# TSAL.net
KiCad netlist of a schematic drawn in Altium Designer
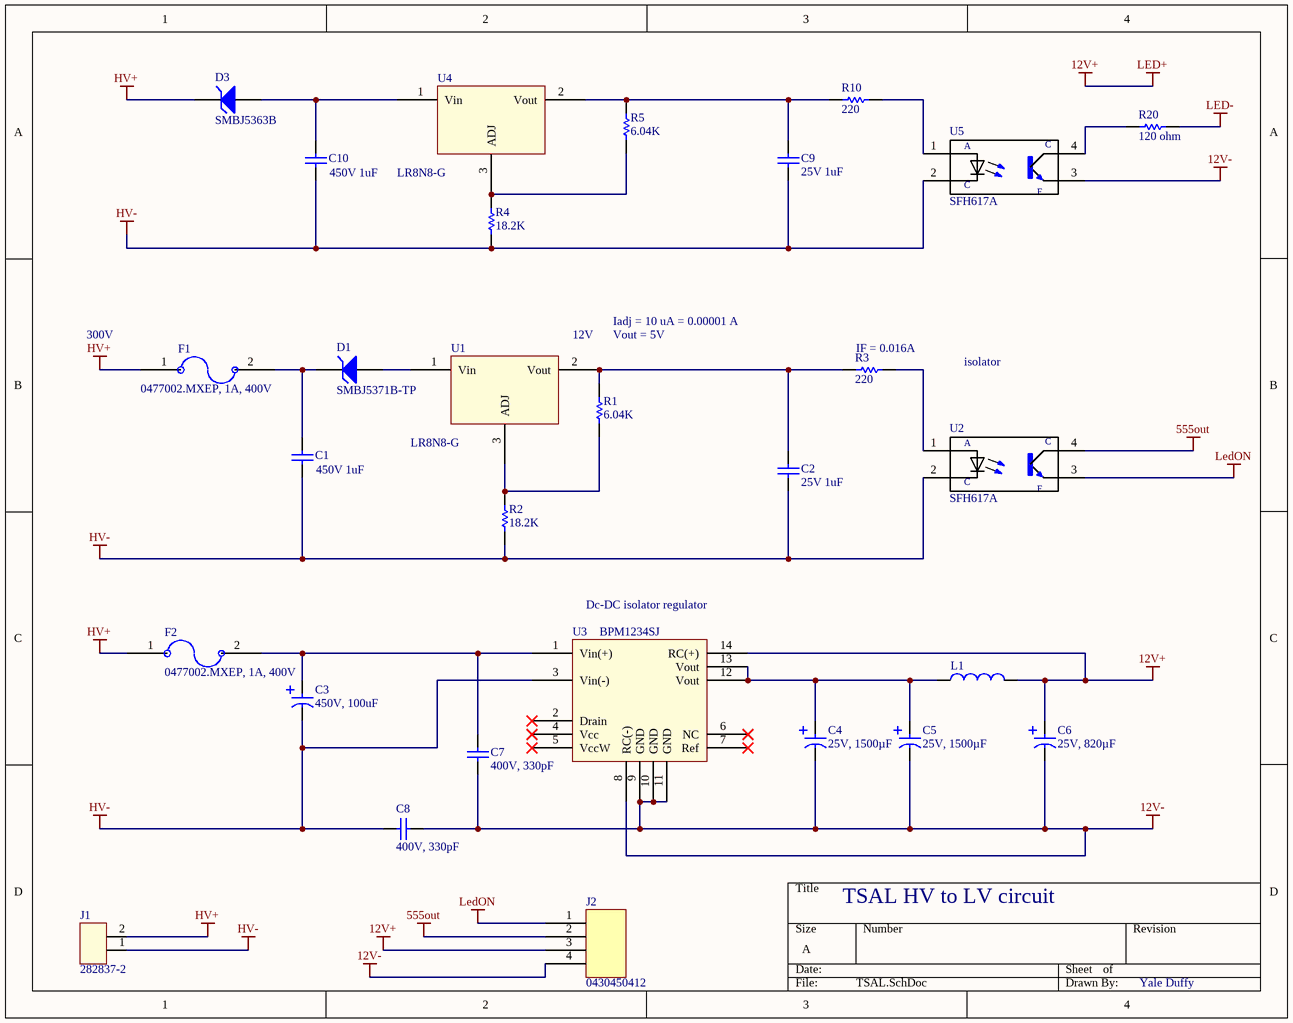
[diagram p0: TSAL.SchDoc]

(export (version "E")
  (design (tool "Eeschema 10.0.6"))
  (components
    (comp (ref "C1")
      (value "450V 1uF")
      (footprint "CKG57KX7T2W105K335JH")
      (description "Decoupling capacitor")
      (libsource (lib "schematic") (part "CKG57KX7T2W105K335JH"))
    )
    (comp (ref "C2")
      (value "25V 1uF")
      (footprint "C0603C105K3RACTU")
      (description "Capacitor, Ceramic, 1 uF, 25 V, ±10% SMT, 0603")
      (libsource (lib "schematic") (part "C0603C105K3RACTU"))
    )
    (comp (ref "C3")
      (value "450V, 100uF")
      (footprint "450BXW100MEFR18X30")
      (description "Capacitors, Radial, Can, 100µF 450V Aluminum")
      (libsource (lib "schematic") (part "450BXW100MEFR18X30"))
    )
    (comp (ref "C4")
      (value "25V, 1500µF")
      (footprint "25ZLS1500MEFC12.5X20")
      (description "Capacitors, Aluminum Electrolytic, Radial, Can, 1500µF, 25V")
      (libsource (lib "schematic") (part "25ZLS1500MEFC12.5X20"))
    )
    (comp (ref "C5")
      (value "25V, 1500µF")
      (footprint "25ZLS1500MEFC12.5X20")
      (description "Capacitors, Aluminum Electrolytic, Radial, Can, 1500µF, 25V")
      (libsource (lib "schematic") (part "25ZLS1500MEFC12.5X20"))
    )
    (comp (ref "C6")
      (value "25V, 820µF")
      (footprint "ESY827M025AH5AA")
      (description "Capacitors Radial, Can, 820µF 25V Aluminum Electrolytic, 23mOhm @ 100kHz 4000 Hrs @ 105°C")
      (libsource (lib "schematic") (part "ESY827M025AH5AA"))
    )
    (comp (ref "C7")
      (value "400V, 330pF")
      (footprint "DE2B3SA331KN3AY02F")
      (description "Capacitor, 330pF ±10% 400VAC Ceramic Capacitor B Radial, Disc")
      (libsource (lib "schematic") (part "DE2B3SA331KN3AY02F"))
    )
    (comp (ref "C8")
      (value "400V, 330pF")
      (footprint "DE2B3SA331KN3AY02F")
      (description "Capacitor, 330pF ±10% 400VAC Ceramic Capacitor B Radial, Disc")
      (libsource (lib "schematic") (part "DE2B3SA331KN3AY02F"))
    )
    (comp (ref "C9")
      (value "25V 1uF")
      (footprint "C0603C105K3RACTU")
      (description "Capacitor, Ceramic, 1 uF, 25 V, ±10% SMT, 0603")
      (libsource (lib "schematic") (part "C0603C105K3RACTU"))
    )
    (comp (ref "C10")
      (value "450V 1uF")
      (footprint "CKG57KX7T2W105K335JH")
      (description "Decoupling capacitor")
      (libsource (lib "schematic") (part "CKG57KX7T2W105K335JH"))
    )
    (comp (ref "D1")
      (value "SMBJ5371B-TP")
      (footprint "214AA")
      (description "Diode, Zener, 60V 5W ±5% Surface Mount DO-214AA (SMB)")
      (libsource (lib "schematic") (part "SMBJ5371B-TP"))
    )
    (comp (ref "D3")
      (value "SMBJ5363B")
      (footprint "214AA")
      (description "Diode Zener 30V 5W ±5% Surface Mount DO-214AA (SMB)")
      (libsource (lib "schematic") (part "SMBJ5363B"))
    )
    (comp (ref "F1")
      (value "0477002.MXEP, 1A, 400V")
      (footprint "0477002.MXEP")
      (description "Fuse, 2A 500V AC 400V DC Fuse Cartridge, Ceramic Through Hole 5mm x 20mm (Axial)")
      (libsource (lib "schematic") (part "0477002.MXEP"))
    )
    (comp (ref "F2")
      (value "0477002.MXEP, 1A, 400V")
      (footprint "0477002.MXEP")
      (description "Fuse, 2A 500V AC 400V DC Fuse Cartridge, Ceramic Through Hole 5mm x 20mm (Axial)")
      (libsource (lib "schematic") (part "0477002.MXEP"))
    )
    (comp (ref "J1")
      (value "282837-2")
      (footprint "282837-2")
      (description "Connector Terminal Blocks Receptacle 2 Position 5.08mm Solder Straight Thru-Hole 13.5A/Contact")
      (libsource (lib "schematic") (part "282837-2"))
    )
    (comp (ref "J2")
      (value "0430450412")
      (footprint "0430450412")
      (description "Connector Header Through Hole 4 position 0.118\" (3.00mm)")
      (libsource (lib "schematic") (part "0430450412"))
    )
    (comp (ref "L1")
      (value "1267AY-2R2N=P3")
      (footprint "1267AY2R2NP3")
      (description "Shielded Wirewound Inductor, 2.2µH ,7.4A 13.2mOhm Max Nonstandard")
      (libsource (lib "schematic") (part "1267AY-2R2N=P3"))
    )
    (comp (ref "R1")
      (value "6.04K")
      (footprint "Resistor 0603")
      (libsource (lib "schematic") (part "ERJ-3EKF6041V"))
    )
    (comp (ref "R2")
      (value "18.2K")
      (footprint "Resistor 0603")
      (description "Resistor, 18.2K ohms, 0603, SMD")
      (libsource (lib "schematic") (part "ERJ-3EKF1822V"))
    )
    (comp (ref "R3")
      (value "220")
      (footprint "Resistor 0603")
      (description "Resistor, 220 ohm, 0603")
      (libsource (lib "schematic") (part "ERJ-3EKF2200V"))
    )
    (comp (ref "R4")
      (value "18.2K")
      (footprint "Resistor 0603")
      (description "Resistor, 18.2K ohms, 0603, SMD")
      (libsource (lib "schematic") (part "ERJ-3EKF1822V"))
    )
    (comp (ref "R5")
      (value "6.04K")
      (footprint "Resistor 0603")
      (libsource (lib "schematic") (part "ERJ-3EKF6041V"))
    )
    (comp (ref "R10")
      (value "220")
      (footprint "Resistor 0603")
      (description "Resistor, 220 ohm, 0603")
      (libsource (lib "schematic") (part "ERJ-3EKF2200V"))
    )
    (comp (ref "R20")
      (value "120 ohm")
      (footprint "Resistor 0603")
      (description "Resistor, 120 ohms, 0603, SMD")
      (libsource (lib "schematic") (part "ERJ-3EKF1200V"))
    )
    (comp (ref "U1")
      (value "LR8N8-G")
      (footprint "TO-243AA(SOT-89-3)")
      (description "Voltage Regulator, Linear, input max 480V, output 1.2V - 440V, TO-243AA , SMD")
      (libsource (lib "schematic") (part "LR8N8-G"))
    )
    (comp (ref "U2")
      (value "SFH617A")
      (footprint "SFH617A")
      (description "opto-Isolator")
      (libsource (lib "schematic") (part "SFH617A"))
    )
    (comp (ref "U3")
      (value "BPM1234SJ")
      (footprint "BPM1234SJ")
      (description "Isolated DC-DC converters, 12 V, 3.4A")
      (libsource (lib "schematic") (part "BPM1234SJ"))
    )
    (comp (ref "U4")
      (value "LR8N8-G")
      (footprint "TO-243AA(SOT-89-3)")
      (description "Voltage Regulator, Linear, input max 480V, output 1.2V - 440V, TO-243AA , SMD")
      (libsource (lib "schematic") (part "LR8N8-G"))
    )
    (comp (ref "U5")
      (value "SFH617A")
      (footprint "SFH617A")
      (description "opto-Isolator")
      (libsource (lib "schematic") (part "SFH617A"))
    )
  )
  (nets
    (net (code "1") (name "12V+") (class "Default")
      (node (ref "C6") (pin "2") (pintype "passive"))
      (node (ref "J2") (pin "3") (pinfunction "3_3") (pintype "passive"))
      (node (ref "L1") (pin "2") (pinfunction "2_2") (pintype "passive"))
      (node (ref "U3") (pin "14") (pinfunction "RC(+)_14") (pintype "passive"))
    )
    (net (code "2") (name "12V-") (class "Default")
      (node (ref "C4") (pin "1") (pintype "passive"))
      (node (ref "C5") (pin "1") (pintype "passive"))
      (node (ref "C6") (pin "1") (pintype "passive"))
      (node (ref "C7") (pin "1") (pintype "passive"))
      (node (ref "C8") (pin "1") (pintype "passive"))
      (node (ref "J2") (pin "4") (pinfunction "4_4") (pintype "passive"))
      (node (ref "U3") (pin "10") (pinfunction "GND_10") (pintype "passive"))
      (node (ref "U3") (pin "11") (pinfunction "GND_11") (pintype "passive"))
      (node (ref "U3") (pin "8") (pinfunction "RC(-)_8") (pintype "passive"))
      (node (ref "U3") (pin "9") (pinfunction "GND_9") (pintype "passive"))
      (node (ref "U5") (pin "3") (pinfunction "E_3") (pintype "passive"))
    )
    (net (code "3") (name "555out") (class "Default")
      (node (ref "J2") (pin "2") (pinfunction "2_2") (pintype "passive"))
      (node (ref "U2") (pin "4") (pinfunction "CO_4") (pintype "passive"))
    )
    (net (code "4") (name "HV+") (class "Default")
      (node (ref "D3") (pin "1") (pinfunction "K_1") (pintype "passive"))
      (node (ref "F1") (pin "1") (pinfunction "1_1") (pintype "passive"))
      (node (ref "F2") (pin "1") (pinfunction "1_1") (pintype "passive"))
      (node (ref "J1") (pin "2") (pinfunction "2_2") (pintype "passive"))
    )
    (net (code "5") (name "HV-") (class "Default")
      (node (ref "C1") (pin "1") (pintype "passive"))
      (node (ref "C10") (pin "1") (pintype "passive"))
      (node (ref "C2") (pin "1") (pintype "passive"))
      (node (ref "C3") (pin "1") (pintype "passive"))
      (node (ref "C8") (pin "2") (pintype "passive"))
      (node (ref "C9") (pin "1") (pintype "passive"))
      (node (ref "J1") (pin "1") (pinfunction "1_1") (pintype "passive"))
      (node (ref "R2") (pin "2") (pinfunction "2_2") (pintype "passive"))
      (node (ref "R4") (pin "2") (pinfunction "2_2") (pintype "passive"))
      (node (ref "U2") (pin "2") (pinfunction "C_2") (pintype "passive"))
      (node (ref "U3") (pin "3") (pinfunction "Vin(-)_3") (pintype "passive"))
      (node (ref "U5") (pin "2") (pinfunction "C_2") (pintype "passive"))
    )
    (net (code "6") (name "LED-") (class "Default")
      (node (ref "R20") (pin "2") (pinfunction "2_2") (pintype "passive"))
    )
    (net (code "7") (name "LedON") (class "Default")
      (node (ref "J2") (pin "1") (pinfunction "1_1") (pintype "passive"))
      (node (ref "U2") (pin "3") (pinfunction "E_3") (pintype "passive"))
    )
    (net (code "8") (name "Net-(C4-Pad2)") (class "Default")
      (node (ref "C4") (pin "2") (pintype "passive"))
      (node (ref "C5") (pin "2") (pintype "passive"))
      (node (ref "L1") (pin "1") (pinfunction "1_1") (pintype "passive"))
      (node (ref "U3") (pin "12") (pinfunction "Vout_12") (pintype "passive"))
      (node (ref "U3") (pin "13") (pinfunction "Vout_13") (pintype "passive"))
    )
    (net (code "9") (name "Net-(D1-A)") (class "Default")
      (node (ref "D1") (pin "2") (pinfunction "A_2") (pintype "passive"))
      (node (ref "U1") (pin "1") (pinfunction "Vin_1") (pintype "passive"))
    )
    (net (code "10") (name "Net-(D1-K)") (class "Default")
      (node (ref "C1") (pin "2") (pintype "passive"))
      (node (ref "D1") (pin "1") (pinfunction "K_1") (pintype "passive"))
      (node (ref "F1") (pin "2") (pinfunction "2_2") (pintype "passive"))
    )
    (net (code "11") (name "Net-(D3-A)") (class "Default")
      (node (ref "C10") (pin "2") (pintype "passive"))
      (node (ref "D3") (pin "2") (pinfunction "A_2") (pintype "passive"))
      (node (ref "U4") (pin "1") (pinfunction "Vin_1") (pintype "passive"))
    )
    (net (code "12") (name "Net-(U1-ADJ)") (class "Default")
      (node (ref "R1") (pin "2") (pinfunction "2_2") (pintype "passive"))
      (node (ref "R2") (pin "1") (pinfunction "1_1") (pintype "passive"))
      (node (ref "U1") (pin "3") (pinfunction "ADJ_3") (pintype "passive"))
    )
    (net (code "13") (name "Net-(U1-Vout)") (class "Default")
      (node (ref "C2") (pin "2") (pintype "passive"))
      (node (ref "R1") (pin "1") (pinfunction "1_1") (pintype "passive"))
      (node (ref "R3") (pin "1") (pinfunction "1_1") (pintype "passive"))
      (node (ref "U1") (pin "2") (pinfunction "Vout_2") (pintype "passive"))
    )
    (net (code "14") (name "Net-(U2-A)") (class "Default")
      (node (ref "R3") (pin "2") (pinfunction "2_2") (pintype "passive"))
      (node (ref "U2") (pin "1") (pinfunction "A_1") (pintype "passive"))
    )
    (net (code "15") (name "Net-(U3-Vin(+))") (class "Default")
      (node (ref "C3") (pin "2") (pintype "passive"))
      (node (ref "C7") (pin "2") (pintype "passive"))
      (node (ref "F2") (pin "2") (pinfunction "2_2") (pintype "passive"))
      (node (ref "U3") (pin "1") (pinfunction "Vin(+)_1") (pintype "passive"))
    )
    (net (code "16") (name "Net-(U4-ADJ)") (class "Default")
      (node (ref "R4") (pin "1") (pinfunction "1_1") (pintype "passive"))
      (node (ref "R5") (pin "2") (pinfunction "2_2") (pintype "passive"))
      (node (ref "U4") (pin "3") (pinfunction "ADJ_3") (pintype "passive"))
    )
    (net (code "17") (name "Net-(U4-Vout)") (class "Default")
      (node (ref "C9") (pin "2") (pintype "passive"))
      (node (ref "R10") (pin "1") (pinfunction "1_1") (pintype "passive"))
      (node (ref "R5") (pin "1") (pinfunction "1_1") (pintype "passive"))
      (node (ref "U4") (pin "2") (pinfunction "Vout_2") (pintype "passive"))
    )
    (net (code "18") (name "Net-(U5-A)") (class "Default")
      (node (ref "R10") (pin "2") (pinfunction "2_2") (pintype "passive"))
      (node (ref "U5") (pin "1") (pinfunction "A_1") (pintype "passive"))
    )
    (net (code "19") (name "Net-(U5-CO)") (class "Default")
      (node (ref "R20") (pin "1") (pinfunction "1_1") (pintype "passive"))
      (node (ref "U5") (pin "4") (pinfunction "CO_4") (pintype "passive"))
    )
    (net (code "20") (name "unconnected-(U3-Drain-Pad2)") (class "Default")
      (node (ref "U3") (pin "2") (pinfunction "Drain_2") (pintype "passive+no_connect"))
    )
    (net (code "21") (name "unconnected-(U3-NC-Pad6)") (class "Default")
      (node (ref "U3") (pin "6") (pinfunction "NC_6") (pintype "passive+no_connect"))
    )
    (net (code "22") (name "unconnected-(U3-Ref-Pad7)") (class "Default")
      (node (ref "U3") (pin "7") (pinfunction "Ref_7") (pintype "passive+no_connect"))
    )
    (net (code "23") (name "unconnected-(U3-Vcc-Pad4)") (class "Default")
      (node (ref "U3") (pin "4") (pinfunction "Vcc_4") (pintype "passive+no_connect"))
    )
    (net (code "24") (name "unconnected-(U3-VccW-Pad5)") (class "Default")
      (node (ref "U3") (pin "5") (pinfunction "VccW_5") (pintype "passive+no_connect"))
    )
  )
)
